# od3.net
KiCad netlist of a schematic drawn in EAGLE
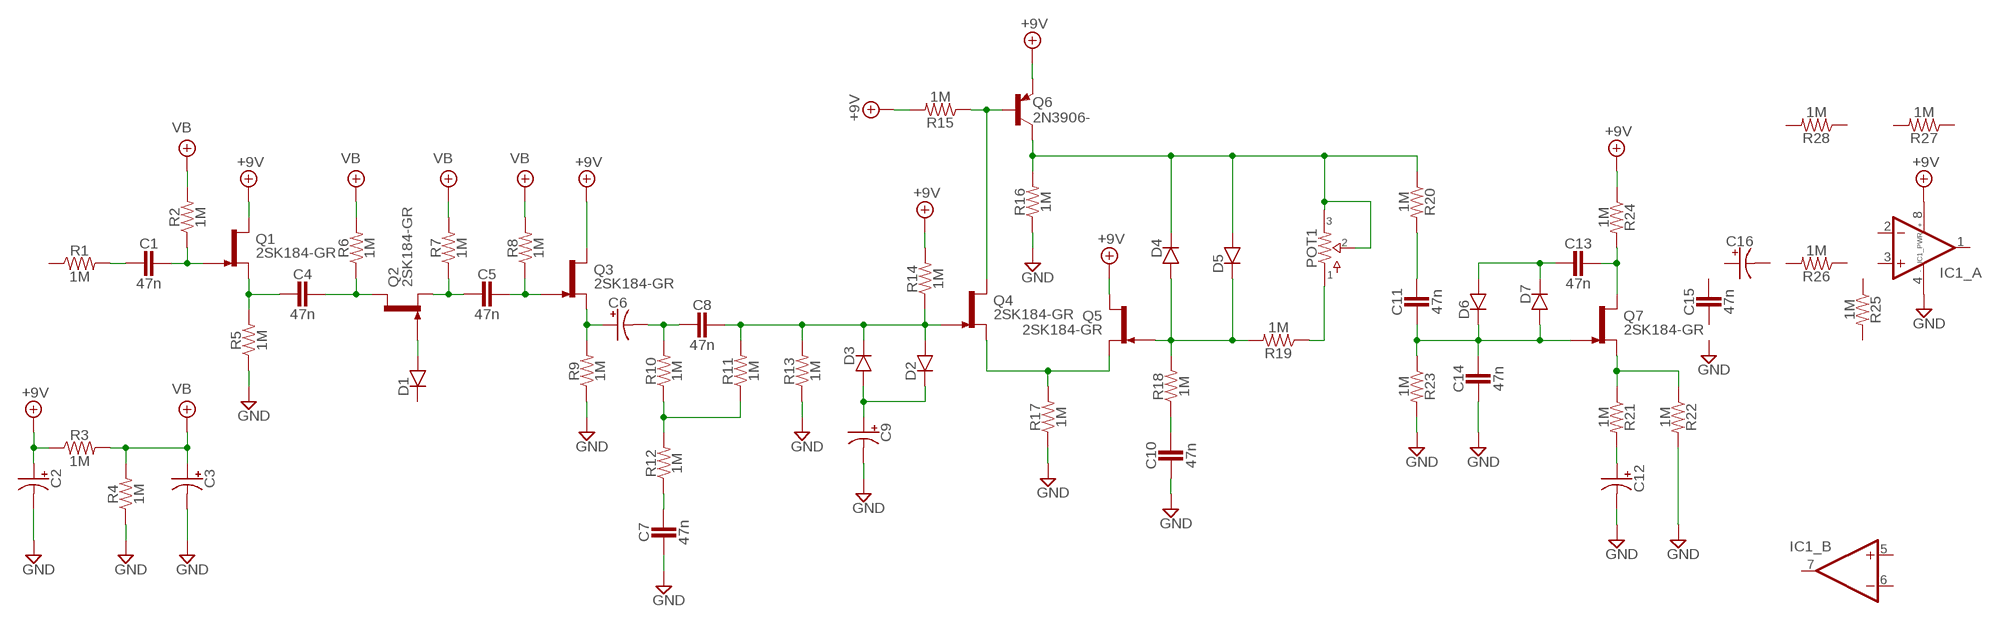
[diagram p0: schematic, sheet 1]

(export (version "E")
  (design (tool "Eeschema 10.0.6"))
  (components
    (comp (ref "C1")
      (value "47n")
      (footprint "eagle-import:BOX_SMALL")
      (libsource (lib "eagle-import") (part "CER/FILMBOX.1"))
    )
    (comp (ref "C2")
      (value "0500")
      (footprint "eagle-import:050_020")
      (libsource (lib "eagle-import") (part "0500"))
    )
    (comp (ref "C3")
      (value "0500")
      (footprint "eagle-import:050_020")
      (libsource (lib "eagle-import") (part "0500"))
    )
    (comp (ref "C4")
      (value "47n")
      (footprint "eagle-import:BOX_SMALL")
      (libsource (lib "eagle-import") (part "CER/FILMBOX.1"))
    )
    (comp (ref "C5")
      (value "47n")
      (footprint "eagle-import:BOX_SMALL")
      (libsource (lib "eagle-import") (part "CER/FILMBOX.1"))
    )
    (comp (ref "C6")
      (value "0500")
      (footprint "eagle-import:050_020")
      (libsource (lib "eagle-import") (part "0500"))
    )
    (comp (ref "C7")
      (value "47n")
      (footprint "eagle-import:BOX_SMALL")
      (libsource (lib "eagle-import") (part "CER/FILMBOX.1"))
    )
    (comp (ref "C8")
      (value "47n")
      (footprint "eagle-import:BOX_SMALL")
      (libsource (lib "eagle-import") (part "CER/FILMBOX.1"))
    )
    (comp (ref "C9")
      (value "0500")
      (footprint "eagle-import:050_020")
      (libsource (lib "eagle-import") (part "0500"))
    )
    (comp (ref "C10")
      (value "47n")
      (footprint "eagle-import:BOX_SMALL")
      (libsource (lib "eagle-import") (part "CER/FILMBOX.1"))
    )
    (comp (ref "C11")
      (value "47n")
      (footprint "eagle-import:BOX_SMALL")
      (libsource (lib "eagle-import") (part "CER/FILMBOX.1"))
    )
    (comp (ref "C12")
      (value "0500")
      (footprint "eagle-import:050_020")
      (libsource (lib "eagle-import") (part "0500"))
    )
    (comp (ref "C13")
      (value "47n")
      (footprint "eagle-import:BOX_SMALL")
      (libsource (lib "eagle-import") (part "CER/FILMBOX.1"))
    )
    (comp (ref "C14")
      (value "47n")
      (footprint "eagle-import:BOX_SMALL")
      (libsource (lib "eagle-import") (part "CER/FILMBOX.1"))
    )
    (comp (ref "C15")
      (value "47n")
      (footprint "eagle-import:BOX_SMALL")
      (libsource (lib "eagle-import") (part "CER/FILMBOX.1"))
    )
    (comp (ref "C16")
      (value "0500")
      (footprint "eagle-import:050_020")
      (libsource (lib "eagle-import") (part "0500"))
    )
    (comp (ref "D1")
      (value "DO35.2")
      (footprint "eagle-import:DO35-2")
      (libsource (lib "eagle-import") (part "DO35.2"))
    )
    (comp (ref "D2")
      (value "DO35.2")
      (footprint "eagle-import:DO35-2")
      (libsource (lib "eagle-import") (part "DO35.2"))
    )
    (comp (ref "D3")
      (value "DO35.2")
      (footprint "eagle-import:DO35-2")
      (libsource (lib "eagle-import") (part "DO35.2"))
    )
    (comp (ref "D4")
      (value "DO35.2")
      (footprint "eagle-import:DO35-2")
      (libsource (lib "eagle-import") (part "DO35.2"))
    )
    (comp (ref "D5")
      (value "DO35.2")
      (footprint "eagle-import:DO35-2")
      (libsource (lib "eagle-import") (part "DO35.2"))
    )
    (comp (ref "D6")
      (value "DO35.2")
      (footprint "eagle-import:DO35-2")
      (libsource (lib "eagle-import") (part "DO35.2"))
    )
    (comp (ref "D7")
      (value "DO35.2")
      (footprint "eagle-import:DO35-2")
      (libsource (lib "eagle-import") (part "DO35.2"))
    )
    (comp (ref "IC1")
      (value "DUALTH")
      (footprint "eagle-import:DIL0")
      (libsource (lib "eagle-import") (part "DUALTH"))
    )
    (comp (ref "POT1")
      (value "POTS16MM")
      (footprint "eagle-import:16MM")
      (libsource (lib "eagle-import") (part "POTS16MM"))
    )
    (comp (ref "Q1")
      (value "2SK184-GR")
      (footprint "eagle-import:TO92-")
      (libsource (lib "eagle-import") (part "2N3819TO-92S"))
    )
    (comp (ref "Q2")
      (value "2SK184-GR")
      (footprint "eagle-import:TO92-")
      (libsource (lib "eagle-import") (part "2N3819TO-92S"))
    )
    (comp (ref "Q3")
      (value "2SK184-GR")
      (footprint "eagle-import:TO92-")
      (libsource (lib "eagle-import") (part "2N3819TO-92S"))
    )
    (comp (ref "Q4")
      (value "2SK184-GR")
      (footprint "eagle-import:TO92-")
      (libsource (lib "eagle-import") (part "2N3819TO-92S"))
    )
    (comp (ref "Q5")
      (value "2SK184-GR")
      (footprint "eagle-import:TO92-")
      (libsource (lib "eagle-import") (part "2N3819TO-92S"))
    )
    (comp (ref "Q6")
      (value "2N3906-")
      (footprint "eagle-import:TO92-")
      (libsource (lib "eagle-import") (part "2N3906-"))
    )
    (comp (ref "Q7")
      (value "2SK184-GR")
      (footprint "eagle-import:TO92-")
      (libsource (lib "eagle-import") (part "2N3819TO-92S"))
    )
    (comp (ref "R1")
      (value "1M")
      (footprint "eagle-import:R0207_3")
      (libsource (lib "eagle-import") (part "R_.3B"))
    )
    (comp (ref "R2")
      (value "1M")
      (footprint "eagle-import:R0207_3")
      (libsource (lib "eagle-import") (part "R_.3B"))
    )
    (comp (ref "R3")
      (value "1M")
      (footprint "eagle-import:R0207_3")
      (libsource (lib "eagle-import") (part "R_.3B"))
    )
    (comp (ref "R4")
      (value "1M")
      (footprint "eagle-import:R0207_3")
      (libsource (lib "eagle-import") (part "R_.3B"))
    )
    (comp (ref "R5")
      (value "1M")
      (footprint "eagle-import:R0207_3")
      (libsource (lib "eagle-import") (part "R_.3B"))
    )
    (comp (ref "R6")
      (value "1M")
      (footprint "eagle-import:R0207_3")
      (libsource (lib "eagle-import") (part "R_.3B"))
    )
    (comp (ref "R7")
      (value "1M")
      (footprint "eagle-import:R0207_3")
      (libsource (lib "eagle-import") (part "R_.3B"))
    )
    (comp (ref "R8")
      (value "1M")
      (footprint "eagle-import:R0207_3")
      (libsource (lib "eagle-import") (part "R_.3B"))
    )
    (comp (ref "R9")
      (value "1M")
      (footprint "eagle-import:R0207_3")
      (libsource (lib "eagle-import") (part "R_.3B"))
    )
    (comp (ref "R10")
      (value "1M")
      (footprint "eagle-import:R0207_3")
      (libsource (lib "eagle-import") (part "R_.3B"))
    )
    (comp (ref "R11")
      (value "1M")
      (footprint "eagle-import:R0207_3")
      (libsource (lib "eagle-import") (part "R_.3B"))
    )
    (comp (ref "R12")
      (value "1M")
      (footprint "eagle-import:R0207_3")
      (libsource (lib "eagle-import") (part "R_.3B"))
    )
    (comp (ref "R13")
      (value "1M")
      (footprint "eagle-import:R0207_3")
      (libsource (lib "eagle-import") (part "R_.3B"))
    )
    (comp (ref "R14")
      (value "1M")
      (footprint "eagle-import:R0207_3")
      (libsource (lib "eagle-import") (part "R_.3B"))
    )
    (comp (ref "R15")
      (value "1M")
      (footprint "eagle-import:R0207_3")
      (libsource (lib "eagle-import") (part "R_.3B"))
    )
    (comp (ref "R16")
      (value "1M")
      (footprint "eagle-import:R0207_3")
      (libsource (lib "eagle-import") (part "R_.3B"))
    )
    (comp (ref "R17")
      (value "1M")
      (footprint "eagle-import:R0207_3")
      (libsource (lib "eagle-import") (part "R_.3B"))
    )
    (comp (ref "R18")
      (value "1M")
      (footprint "eagle-import:R0207_3")
      (libsource (lib "eagle-import") (part "R_.3B"))
    )
    (comp (ref "R19")
      (value "1M")
      (footprint "eagle-import:R0207_3")
      (libsource (lib "eagle-import") (part "R_.3B"))
    )
    (comp (ref "R20")
      (value "1M")
      (footprint "eagle-import:R0207_3")
      (libsource (lib "eagle-import") (part "R_.3B"))
    )
    (comp (ref "R21")
      (value "1M")
      (footprint "eagle-import:R0207_3")
      (libsource (lib "eagle-import") (part "R_.3B"))
    )
    (comp (ref "R22")
      (value "1M")
      (footprint "eagle-import:R0207_3")
      (libsource (lib "eagle-import") (part "R_.3B"))
    )
    (comp (ref "R23")
      (value "1M")
      (footprint "eagle-import:R0207_3")
      (libsource (lib "eagle-import") (part "R_.3B"))
    )
    (comp (ref "R24")
      (value "1M")
      (footprint "eagle-import:R0207_3")
      (libsource (lib "eagle-import") (part "R_.3B"))
    )
    (comp (ref "R25")
      (value "1M")
      (footprint "eagle-import:R0207_3")
      (libsource (lib "eagle-import") (part "R_.3B"))
    )
    (comp (ref "R26")
      (value "1M")
      (footprint "eagle-import:R0207_3")
      (libsource (lib "eagle-import") (part "R_.3B"))
    )
    (comp (ref "R27")
      (value "1M")
      (footprint "eagle-import:R0207_3")
      (libsource (lib "eagle-import") (part "R_.3B"))
    )
    (comp (ref "R28")
      (value "1M")
      (footprint "eagle-import:R0207_3")
      (libsource (lib "eagle-import") (part "R_.3B"))
    )
  )
  (nets
    (net (code "1") (name "+9V") (class "Default")
      (node (ref "C2") (pin "+") (pinfunction "+_+") (pintype "passive"))
      (node (ref "IC1") (pin "8") (pinfunction "V+_8") (pintype "power_in"))
      (node (ref "Q1") (pin "3") (pinfunction "D_3") (pintype "passive"))
      (node (ref "Q3") (pin "3") (pinfunction "D_3") (pintype "passive"))
      (node (ref "Q5") (pin "3") (pinfunction "D_3") (pintype "passive"))
      (node (ref "Q6") (pin "3") (pinfunction "E_3") (pintype "passive"))
      (node (ref "R14") (pin "2") (pinfunction "2_2") (pintype "passive"))
      (node (ref "R15") (pin "2") (pinfunction "2_2") (pintype "passive"))
      (node (ref "R24") (pin "1") (pinfunction "1_1") (pintype "passive"))
      (node (ref "R3") (pin "1") (pinfunction "1_1") (pintype "passive"))
    )
    (net (code "2") (name "GND") (class "Default")
      (node (ref "C10") (pin "2") (pinfunction "2_2") (pintype "passive"))
      (node (ref "C12") (pin "-") (pinfunction "-_-") (pintype "passive"))
      (node (ref "C14") (pin "2") (pinfunction "2_2") (pintype "passive"))
      (node (ref "C2") (pin "-") (pinfunction "-_-") (pintype "passive"))
      (node (ref "C3") (pin "-") (pinfunction "-_-") (pintype "passive"))
      (node (ref "C7") (pin "2") (pinfunction "2_2") (pintype "passive"))
      (node (ref "C9") (pin "-") (pinfunction "-_-") (pintype "passive"))
      (node (ref "IC1") (pin "4") (pinfunction "V-_4") (pintype "power_in"))
      (node (ref "R13") (pin "1") (pinfunction "1_1") (pintype "passive"))
      (node (ref "R16") (pin "1") (pinfunction "1_1") (pintype "passive"))
      (node (ref "R17") (pin "1") (pinfunction "1_1") (pintype "passive"))
      (node (ref "R22") (pin "2") (pinfunction "2_2") (pintype "passive"))
      (node (ref "R23") (pin "2") (pinfunction "2_2") (pintype "passive"))
      (node (ref "R4") (pin "1") (pinfunction "1_1") (pintype "passive"))
      (node (ref "R5") (pin "1") (pinfunction "1_1") (pintype "passive"))
      (node (ref "R9") (pin "1") (pinfunction "1_1") (pintype "passive"))
    )
    (net (code "3") (name "Net-(C1-Pad2)") (class "Default")
      (node (ref "C1") (pin "2") (pinfunction "2_2") (pintype "passive"))
      (node (ref "R1") (pin "2") (pinfunction "2_2") (pintype "passive"))
    )
    (net (code "4") (name "Net-(C6-Pad-)") (class "Default")
      (node (ref "C6") (pin "-") (pinfunction "-_-") (pintype "passive"))
      (node (ref "C8") (pin "2") (pinfunction "2_2") (pintype "passive"))
      (node (ref "R10") (pin "2") (pinfunction "2_2") (pintype "passive"))
    )
    (net (code "5") (name "Net-(C7-Pad1)") (class "Default")
      (node (ref "C7") (pin "1") (pinfunction "1_1") (pintype "passive"))
      (node (ref "R12") (pin "1") (pinfunction "1_1") (pintype "passive"))
    )
    (net (code "6") (name "Net-(C9-Pad+)") (class "Default")
      (node (ref "C9") (pin "+") (pinfunction "+_+") (pintype "passive"))
      (node (ref "D2") (pin "C") (pinfunction "C_C") (pintype "passive"))
      (node (ref "D3") (pin "A") (pinfunction "A_A") (pintype "passive"))
    )
    (net (code "7") (name "Net-(C10-Pad1)") (class "Default")
      (node (ref "C10") (pin "1") (pinfunction "1_1") (pintype "passive"))
      (node (ref "R18") (pin "1") (pinfunction "1_1") (pintype "passive"))
    )
    (net (code "8") (name "Net-(C11-Pad1)") (class "Default")
      (node (ref "C11") (pin "1") (pinfunction "1_1") (pintype "passive"))
      (node (ref "R20") (pin "2") (pinfunction "2_2") (pintype "passive"))
    )
    (net (code "9") (name "Net-(C12-Pad+)") (class "Default")
      (node (ref "C12") (pin "+") (pinfunction "+_+") (pintype "passive"))
      (node (ref "R21") (pin "2") (pinfunction "2_2") (pintype "passive"))
    )
    (net (code "10") (name "Net-(C13-Pad2)") (class "Default")
      (node (ref "C13") (pin "2") (pinfunction "2_2") (pintype "passive"))
      (node (ref "D6") (pin "A") (pinfunction "A_A") (pintype "passive"))
      (node (ref "D7") (pin "C") (pinfunction "C_C") (pintype "passive"))
    )
    (net (code "11") (name "Net-(POT1-Pad1)") (class "Default")
      (node (ref "POT1") (pin "1") (pinfunction "1_1") (pintype "passive"))
      (node (ref "R19") (pin "1") (pinfunction "1_1") (pintype "passive"))
    )
    (net (code "12") (name "Net-(Q1-G)") (class "Default")
      (node (ref "C1") (pin "1") (pinfunction "1_1") (pintype "passive"))
      (node (ref "Q1") (pin "2") (pinfunction "G_2") (pintype "passive"))
      (node (ref "R2") (pin "1") (pinfunction "1_1") (pintype "passive"))
    )
    (net (code "13") (name "Net-(Q1-S)") (class "Default")
      (node (ref "C4") (pin "2") (pinfunction "2_2") (pintype "passive"))
      (node (ref "Q1") (pin "1") (pinfunction "S_1") (pintype "passive"))
      (node (ref "R5") (pin "2") (pinfunction "2_2") (pintype "passive"))
    )
    (net (code "14") (name "Net-(Q2-D)") (class "Default")
      (node (ref "C4") (pin "1") (pinfunction "1_1") (pintype "passive"))
      (node (ref "Q2") (pin "3") (pinfunction "D_3") (pintype "passive"))
      (node (ref "R6") (pin "1") (pinfunction "1_1") (pintype "passive"))
    )
    (net (code "15") (name "Net-(Q2-G)") (class "Default")
      (node (ref "D1") (pin "A") (pinfunction "A_A") (pintype "passive"))
      (node (ref "Q2") (pin "2") (pinfunction "G_2") (pintype "passive"))
    )
    (net (code "16") (name "Net-(Q2-S)") (class "Default")
      (node (ref "C5") (pin "2") (pinfunction "2_2") (pintype "passive"))
      (node (ref "Q2") (pin "1") (pinfunction "S_1") (pintype "passive"))
      (node (ref "R7") (pin "1") (pinfunction "1_1") (pintype "passive"))
    )
    (net (code "17") (name "Net-(Q3-G)") (class "Default")
      (node (ref "C5") (pin "1") (pinfunction "1_1") (pintype "passive"))
      (node (ref "Q3") (pin "2") (pinfunction "G_2") (pintype "passive"))
      (node (ref "R8") (pin "1") (pinfunction "1_1") (pintype "passive"))
    )
    (net (code "18") (name "Net-(Q3-S)") (class "Default")
      (node (ref "C6") (pin "+") (pinfunction "+_+") (pintype "passive"))
      (node (ref "Q3") (pin "1") (pinfunction "S_1") (pintype "passive"))
      (node (ref "R9") (pin "2") (pinfunction "2_2") (pintype "passive"))
    )
    (net (code "19") (name "Net-(Q4-D)") (class "Default")
      (node (ref "Q4") (pin "3") (pinfunction "D_3") (pintype "passive"))
      (node (ref "Q6") (pin "2") (pinfunction "B_2") (pintype "passive"))
      (node (ref "R15") (pin "1") (pinfunction "1_1") (pintype "passive"))
    )
    (net (code "20") (name "Net-(Q4-G)") (class "Default")
      (node (ref "C8") (pin "1") (pinfunction "1_1") (pintype "passive"))
      (node (ref "D2") (pin "A") (pinfunction "A_A") (pintype "passive"))
      (node (ref "D3") (pin "C") (pinfunction "C_C") (pintype "passive"))
      (node (ref "Q4") (pin "2") (pinfunction "G_2") (pintype "passive"))
      (node (ref "R11") (pin "2") (pinfunction "2_2") (pintype "passive"))
      (node (ref "R13") (pin "2") (pinfunction "2_2") (pintype "passive"))
      (node (ref "R14") (pin "1") (pinfunction "1_1") (pintype "passive"))
    )
    (net (code "21") (name "Net-(Q4-S)") (class "Default")
      (node (ref "Q4") (pin "1") (pinfunction "S_1") (pintype "passive"))
      (node (ref "Q5") (pin "1") (pinfunction "S_1") (pintype "passive"))
      (node (ref "R17") (pin "2") (pinfunction "2_2") (pintype "passive"))
    )
    (net (code "22") (name "Net-(Q5-G)") (class "Default")
      (node (ref "D4") (pin "A") (pinfunction "A_A") (pintype "passive"))
      (node (ref "D5") (pin "C") (pinfunction "C_C") (pintype "passive"))
      (node (ref "Q5") (pin "2") (pinfunction "G_2") (pintype "passive"))
      (node (ref "R18") (pin "2") (pinfunction "2_2") (pintype "passive"))
      (node (ref "R19") (pin "2") (pinfunction "2_2") (pintype "passive"))
    )
    (net (code "23") (name "Net-(Q6-C)") (class "Default")
      (node (ref "D4") (pin "C") (pinfunction "C_C") (pintype "passive"))
      (node (ref "D5") (pin "A") (pinfunction "A_A") (pintype "passive"))
      (node (ref "POT1") (pin "2") (pinfunction "2_2") (pintype "passive"))
      (node (ref "POT1") (pin "3") (pinfunction "3_3") (pintype "passive"))
      (node (ref "Q6") (pin "1") (pinfunction "C_1") (pintype "passive"))
      (node (ref "R16") (pin "2") (pinfunction "2_2") (pintype "passive"))
      (node (ref "R20") (pin "1") (pinfunction "1_1") (pintype "passive"))
    )
    (net (code "24") (name "Net-(Q7-D)") (class "Default")
      (node (ref "C13") (pin "1") (pinfunction "1_1") (pintype "passive"))
      (node (ref "Q7") (pin "3") (pinfunction "D_3") (pintype "passive"))
      (node (ref "R24") (pin "2") (pinfunction "2_2") (pintype "passive"))
    )
    (net (code "25") (name "Net-(Q7-G)") (class "Default")
      (node (ref "C11") (pin "2") (pinfunction "2_2") (pintype "passive"))
      (node (ref "C14") (pin "1") (pinfunction "1_1") (pintype "passive"))
      (node (ref "D6") (pin "C") (pinfunction "C_C") (pintype "passive"))
      (node (ref "D7") (pin "A") (pinfunction "A_A") (pintype "passive"))
      (node (ref "Q7") (pin "2") (pinfunction "G_2") (pintype "passive"))
      (node (ref "R23") (pin "1") (pinfunction "1_1") (pintype "passive"))
    )
    (net (code "26") (name "Net-(Q7-S)") (class "Default")
      (node (ref "Q7") (pin "1") (pinfunction "S_1") (pintype "passive"))
      (node (ref "R21") (pin "1") (pinfunction "1_1") (pintype "passive"))
      (node (ref "R22") (pin "1") (pinfunction "1_1") (pintype "passive"))
    )
    (net (code "27") (name "Net-(R10-Pad1)") (class "Default")
      (node (ref "R10") (pin "1") (pinfunction "1_1") (pintype "passive"))
      (node (ref "R11") (pin "1") (pinfunction "1_1") (pintype "passive"))
      (node (ref "R12") (pin "2") (pinfunction "2_2") (pintype "passive"))
    )
    (net (code "28") (name "VB") (class "Default")
      (node (ref "C3") (pin "+") (pinfunction "+_+") (pintype "passive"))
      (node (ref "R2") (pin "2") (pinfunction "2_2") (pintype "passive"))
      (node (ref "R3") (pin "2") (pinfunction "2_2") (pintype "passive"))
      (node (ref "R4") (pin "2") (pinfunction "2_2") (pintype "passive"))
      (node (ref "R6") (pin "2") (pinfunction "2_2") (pintype "passive"))
      (node (ref "R7") (pin "2") (pinfunction "2_2") (pintype "passive"))
      (node (ref "R8") (pin "2") (pinfunction "2_2") (pintype "passive"))
    )
    (net (code "29") (name "unconnected-(C15-Pad1)") (class "Default")
      (node (ref "C15") (pin "1") (pinfunction "1_1") (pintype "passive"))
    )
    (net (code "30") (name "unconnected-(C15-Pad2)") (class "Default")
      (node (ref "C15") (pin "2") (pinfunction "2_2") (pintype "passive"))
    )
    (net (code "31") (name "unconnected-(C16-Pad+)") (class "Default")
      (node (ref "C16") (pin "+") (pinfunction "+_+") (pintype "passive"))
    )
    (net (code "32") (name "unconnected-(C16-Pad-)") (class "Default")
      (node (ref "C16") (pin "-") (pinfunction "-_-") (pintype "passive"))
    )
    (net (code "33") (name "unconnected-(D1-PadC)") (class "Default")
      (node (ref "D1") (pin "C") (pinfunction "C_C") (pintype "passive"))
    )
    (net (code "34") (name "unconnected-(IC1A-+IN-Pad3)") (class "Default")
      (node (ref "IC1") (pin "3") (pinfunction "+IN_3") (pintype "input"))
    )
    (net (code "35") (name "unconnected-(IC1A--IN-Pad2)") (class "Default")
      (node (ref "IC1") (pin "2") (pinfunction "-IN_2") (pintype "input"))
    )
    (net (code "36") (name "unconnected-(IC1A-OUT-Pad1)") (class "Default")
      (node (ref "IC1") (pin "1") (pinfunction "OUT_1") (pintype "output"))
    )
    (net (code "37") (name "unconnected-(IC1B-+IN-Pad5)") (class "Default")
      (node (ref "IC1") (pin "5") (pinfunction "+IN_5") (pintype "input"))
    )
    (net (code "38") (name "unconnected-(IC1B--IN-Pad6)") (class "Default")
      (node (ref "IC1") (pin "6") (pinfunction "-IN_6") (pintype "input"))
    )
    (net (code "39") (name "unconnected-(IC1B-OUT-Pad7)") (class "Default")
      (node (ref "IC1") (pin "7") (pinfunction "OUT_7") (pintype "output"))
    )
    (net (code "40") (name "unconnected-(R1-Pad1)") (class "Default")
      (node (ref "R1") (pin "1") (pinfunction "1_1") (pintype "passive"))
    )
    (net (code "41") (name "unconnected-(R25-Pad1)") (class "Default")
      (node (ref "R25") (pin "1") (pinfunction "1_1") (pintype "passive"))
    )
    (net (code "42") (name "unconnected-(R25-Pad2)") (class "Default")
      (node (ref "R25") (pin "2") (pinfunction "2_2") (pintype "passive"))
    )
    (net (code "43") (name "unconnected-(R26-Pad1)") (class "Default")
      (node (ref "R26") (pin "1") (pinfunction "1_1") (pintype "passive"))
    )
    (net (code "44") (name "unconnected-(R26-Pad2)") (class "Default")
      (node (ref "R26") (pin "2") (pinfunction "2_2") (pintype "passive"))
    )
    (net (code "45") (name "unconnected-(R27-Pad1)") (class "Default")
      (node (ref "R27") (pin "1") (pinfunction "1_1") (pintype "passive"))
    )
    (net (code "46") (name "unconnected-(R27-Pad2)") (class "Default")
      (node (ref "R27") (pin "2") (pinfunction "2_2") (pintype "passive"))
    )
    (net (code "47") (name "unconnected-(R28-Pad1)") (class "Default")
      (node (ref "R28") (pin "1") (pinfunction "1_1") (pintype "passive"))
    )
    (net (code "48") (name "unconnected-(R28-Pad2)") (class "Default")
      (node (ref "R28") (pin "2") (pinfunction "2_2") (pintype "passive"))
    )
  )
)
